# ST-LINK.net
KiCad netlist of a schematic drawn in Altium Designer
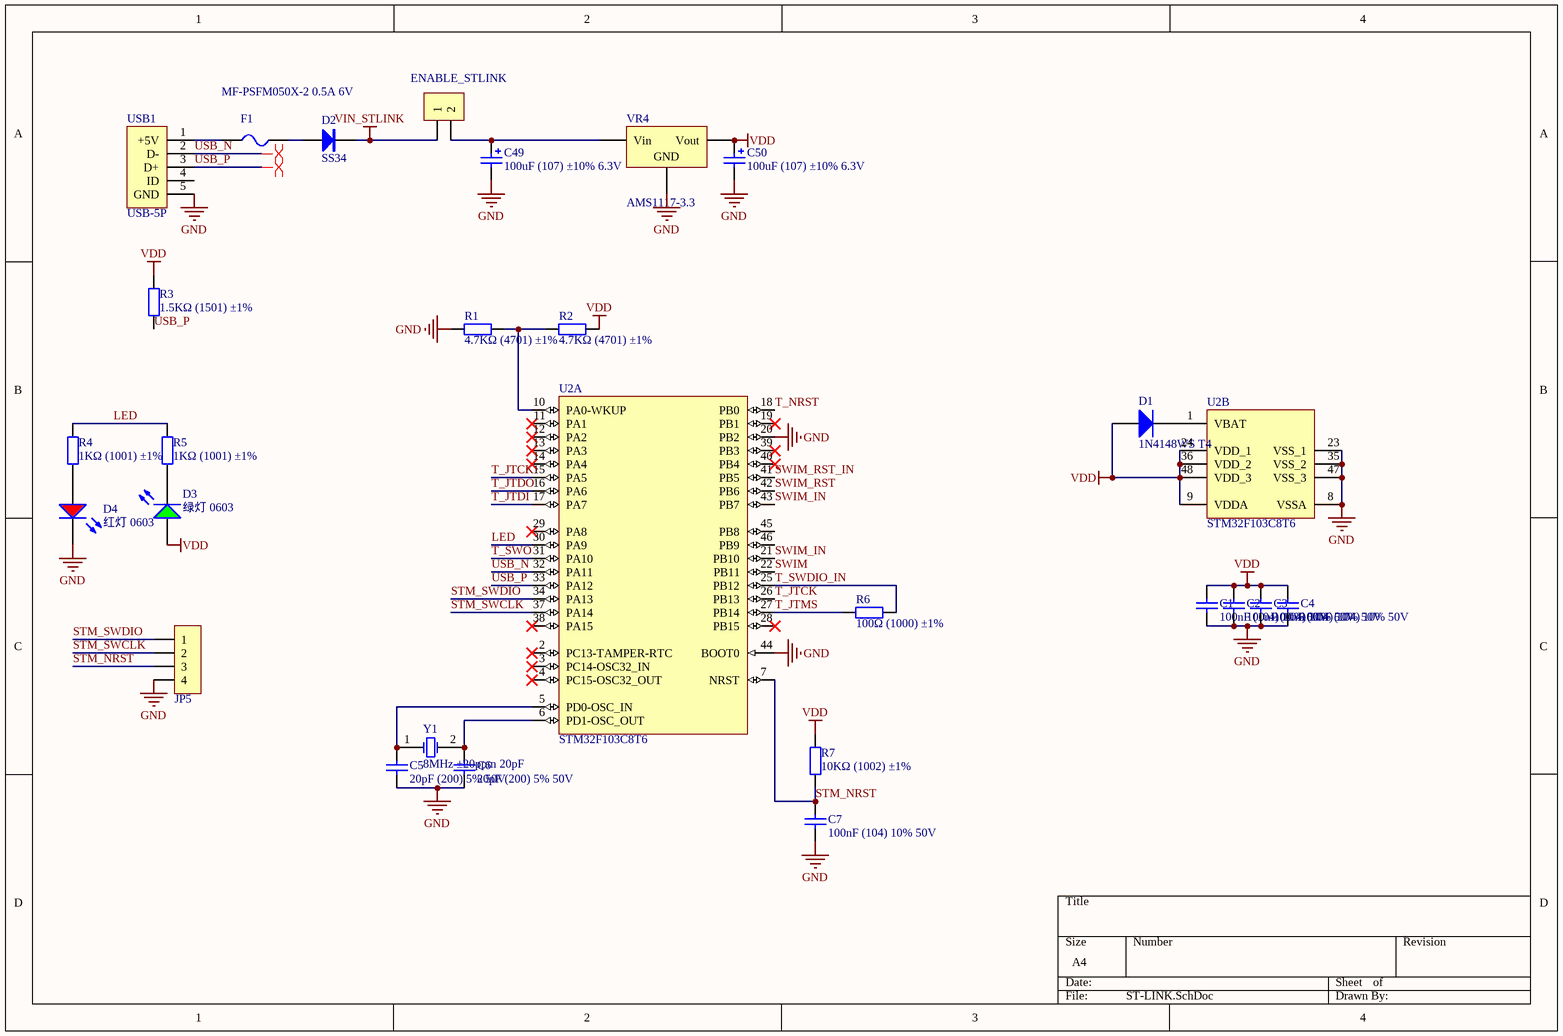
[diagram p0: ST-LINK.SchDoc]

(export (version "E")
  (design (tool "Eeschema 10.0.6"))
  (components
    (comp (ref "C1")
      (value "100nF (104) 10% 50V")
      (footprint "0603_C")
      (description "贴片电容")
      (libsource (lib "Cap") (part "0603 100nF (104) 10% 50V"))
    )
    (comp (ref "C2")
      (value "100nF (104) 10% 50V")
      (footprint "0603_C")
      (description "贴片电容")
      (libsource (lib "Cap") (part "0603 100nF (104) 10% 50V"))
    )
    (comp (ref "C3")
      (value "100nF (104) 10% 50V")
      (footprint "0603_C")
      (description "贴片电容")
      (libsource (lib "Cap") (part "0603 100nF (104) 10% 50V"))
    )
    (comp (ref "C4")
      (value "100nF (104) 10% 50V")
      (footprint "0603_C")
      (description "贴片电容")
      (libsource (lib "Cap") (part "0603 100nF (104) 10% 50V"))
    )
    (comp (ref "C5")
      (value "20pF (200) 5% 50V")
      (footprint "0603_C")
      (description "贴片电容")
      (libsource (lib "Cap") (part "0603 20pF (200) 5% 50V"))
    )
    (comp (ref "C6")
      (value "20pF (200) 5% 50V")
      (footprint "0603_C")
      (description "贴片电容")
      (libsource (lib "Cap") (part "0603 20pF (200) 5% 50V"))
    )
    (comp (ref "C7")
      (value "100nF (104) 10% 50V")
      (footprint "0603_C")
      (description "贴片电容")
      (libsource (lib "Cap") (part "0603 100nF (104) 10% 50V"))
    )
    (comp (ref "C49")
      (value "100uF (107) ±10% 6.3V")
      (footprint "CASE-B_3528")
      (description "钽电容")
      (libsource (lib "Cap") (part "3528 100uF (107) 10% 6.3V"))
    )
    (comp (ref "C50")
      (value "100uF (107) ±10% 6.3V")
      (footprint "CASE-B_3528")
      (description "钽电容")
      (libsource (lib "Cap") (part "3528 100uF (107) 10% 6.3V"))
    )
    (comp (ref "D1")
      (value "1N4148WS T4")
      (footprint "SOD-323")
      (description "二极管")
      (libsource (lib "Diode") (part "SOD-323 1N4148WS T4"))
    )
    (comp (ref "D2")
      (value "SS34")
      (footprint "SMC")
      (description "肖特基二极管")
      (fields (field (name "版权归属") "源创客"))
      (libsource (lib "8.1   - 二极管-整流桥") (part "SS34"))
    )
    (comp (ref "D3")
      (value "绿灯 0603")
      (footprint "0603_LED_S1")
      (description "发光二极管")
      (libsource (lib "LED") (part "0603 绿灯"))
    )
    (comp (ref "D4")
      (value "红灯 0603")
      (footprint "0603_LED_S1")
      (description "发光二极管")
      (libsource (lib "LED") (part "0603 红灯"))
    )
    (comp (ref "ENABLE_STLINK")
      (value "HDR-1X2")
      (footprint "HDR2.54-LI-2P")
      (description "2P接插件")
      (fields (field (name "版权归属") "源创客"))
      (libsource (lib "4.5   - 接插件-脚距2.54") (part "Header 2"))
    )
    (comp (ref "F1")
      (value "MF-PSFM050X-2 0.5A 6V")
      (footprint "FU 0805")
      (description "贴片保险丝")
      (fields (field (name "版权归属") "源创客"))
      (libsource (lib "10.1 - 保险丝-晶振") (part "FU"))
    )
    (comp (ref "JP5")
      (value "HDR-1X4")
      (footprint "HDR2.54-LI-4P")
      (description "4P接插件")
      (fields (field (name "版权归属") "源创客"))
      (libsource (lib "4.5   - 接插件-脚距2.54") (part "Header 4"))
    )
    (comp (ref "R1")
      (value "4.7KΩ (4701) ±1%")
      (footprint "0603_R")
      (description "贴片电阻")
      (libsource (lib "RES") (part "0603 4.7KΩ (4701) 1%"))
    )
    (comp (ref "R2")
      (value "4.7KΩ (4701) ±1%")
      (footprint "0603_R")
      (description "贴片电阻")
      (libsource (lib "RES") (part "0603 4.7KΩ (4701) 1%"))
    )
    (comp (ref "R3")
      (value "1.5KΩ (1501) ±1%")
      (footprint "0603_R")
      (description "贴片电阻")
      (libsource (lib "RES") (part "0603 1.5KΩ (1501) 1%"))
    )
    (comp (ref "R4")
      (value "1KΩ (1001) ±1%")
      (footprint "0603_R")
      (description "贴片电阻")
      (libsource (lib "RES") (part "0603 1KΩ (1001) 1%"))
    )
    (comp (ref "R5")
      (value "1KΩ (1001) ±1%")
      (footprint "0603_R")
      (description "贴片电阻")
      (libsource (lib "RES") (part "0603 1KΩ (1001) 1%"))
    )
    (comp (ref "R6")
      (value "100Ω (1000) ±1%")
      (footprint "0603_R")
      (description "贴片电阻")
      (libsource (lib "RES") (part "0603 100Ω (1000) 1%"))
    )
    (comp (ref "R7")
      (value "10KΩ (1002) ±1%")
      (footprint "0603_R")
      (description "贴片电阻")
      (libsource (lib "RES") (part "0603 10KΩ (1002) 1%"))
    )
    (comp (ref "U2")
      (value "STM32F103C8T6")
      (footprint "STM-LQFP48_L")
      (libsource (lib "Altium Content Vault") (part "MC-ARM-STM32F103X8_B-SQ48"))
    )
    (comp (ref "USB1")
      (value "USB-5P")
      (footprint "USB-MICRO_D")
      (description "微型USB母座")
      (fields (field (name "版权归属") "源创客"))
      (libsource (lib "4.1   - 接口类") (part "USB-5P"))
    )
    (comp (ref "VR4")
      (value "AMS1117-3.3")
      (footprint "SOT-223")
      (description "低压差线性稳压(LDO)")
      (libsource (lib "LDO") (part "SOT-223 AMS1117-3.3"))
    )
    (comp (ref "Y1")
      (value "8MHz ±20ppm 20pF")
      (footprint "SMD-5032_2P")
      (description "贴片晶振")
      (libsource (lib "CrystalOscillator") (part "SMD-5032_2P 8MHz 20ppm 20pF"))
    )
  )
  (nets
    (net (code "1") (name "/LED") (class "Default")
      (node (ref "R4") (pin "2") (pinfunction "2_2") (pintype "passive"))
      (node (ref "R5") (pin "2") (pinfunction "2_2") (pintype "passive"))
      (node (ref "U2") (pin "30") (pinfunction "PA9_30") (pintype "bidirectional"))
    )
    (net (code "2") (name "/STM_NRST") (class "Default")
      (node (ref "C7") (pin "2") (pinfunction "2_2") (pintype "passive"))
      (node (ref "JP5") (pin "3") (pinfunction "3_3") (pintype "passive"))
      (node (ref "R7") (pin "1") (pinfunction "1_1") (pintype "passive"))
      (node (ref "U2") (pin "7") (pinfunction "NRST_7") (pintype "bidirectional"))
    )
    (net (code "3") (name "/STM_SWCLK") (class "Default")
      (node (ref "JP5") (pin "2") (pinfunction "2_2") (pintype "passive"))
      (node (ref "U2") (pin "37") (pinfunction "PA14_37") (pintype "bidirectional"))
    )
    (net (code "4") (name "/STM_SWDIO") (class "Default")
      (node (ref "JP5") (pin "1") (pinfunction "1_1") (pintype "passive"))
      (node (ref "U2") (pin "34") (pinfunction "PA13_34") (pintype "bidirectional"))
    )
    (net (code "5") (name "/SWIM") (class "Default")
      (node (ref "U2") (pin "22") (pinfunction "PB11_22") (pintype "bidirectional"))
    )
    (net (code "6") (name "/SWIM_IN") (class "Default")
      (node (ref "U2") (pin "21") (pinfunction "PB10_21") (pintype "bidirectional"))
      (node (ref "U2") (pin "43") (pinfunction "PB7_43") (pintype "bidirectional"))
    )
    (net (code "7") (name "/SWIM_RST") (class "Default")
      (node (ref "U2") (pin "42") (pinfunction "PB6_42") (pintype "bidirectional"))
    )
    (net (code "8") (name "/SWIM_RST_IN") (class "Default")
      (node (ref "U2") (pin "41") (pinfunction "PB5_41") (pintype "bidirectional"))
    )
    (net (code "9") (name "/T_JTCK") (class "Default")
      (node (ref "U2") (pin "15") (pinfunction "PA5_15") (pintype "bidirectional"))
      (node (ref "U2") (pin "26") (pinfunction "PB13_26") (pintype "bidirectional"))
    )
    (net (code "10") (name "/T_JTDI") (class "Default")
      (node (ref "U2") (pin "17") (pinfunction "PA7_17") (pintype "bidirectional"))
    )
    (net (code "11") (name "/T_JTDO") (class "Default")
      (node (ref "U2") (pin "16") (pinfunction "PA6_16") (pintype "bidirectional"))
    )
    (net (code "12") (name "/T_JTMS") (class "Default")
      (node (ref "R6") (pin "1") (pinfunction "1_1") (pintype "passive"))
      (node (ref "U2") (pin "27") (pinfunction "PB14_27") (pintype "bidirectional"))
    )
    (net (code "13") (name "/T_NRST") (class "Default")
      (node (ref "U2") (pin "18") (pinfunction "PB0_18") (pintype "bidirectional"))
    )
    (net (code "14") (name "/T_SWDIO_IN") (class "Default")
      (node (ref "R6") (pin "2") (pinfunction "2_2") (pintype "passive"))
      (node (ref "U2") (pin "25") (pinfunction "PB12_25") (pintype "bidirectional"))
    )
    (net (code "15") (name "/T_SWO") (class "Default")
      (node (ref "U2") (pin "31") (pinfunction "PA10_31") (pintype "bidirectional"))
    )
    (net (code "16") (name "/USB_N") (class "Default")
      (node (ref "U2") (pin "32") (pinfunction "PA11_32") (pintype "bidirectional"))
      (node (ref "USB1") (pin "2") (pinfunction "D-_2") (pintype "passive"))
    )
    (net (code "17") (name "/USB_P") (class "Default")
      (node (ref "R3") (pin "1") (pinfunction "1_1") (pintype "passive"))
      (node (ref "U2") (pin "33") (pinfunction "PA12_33") (pintype "bidirectional"))
      (node (ref "USB1") (pin "3") (pinfunction "D+_3") (pintype "passive"))
    )
    (net (code "18") (name "GND") (class "Default")
      (node (ref "C1") (pin "1") (pinfunction "1_1") (pintype "passive"))
      (node (ref "C2") (pin "1") (pinfunction "1_1") (pintype "passive"))
      (node (ref "C3") (pin "1") (pinfunction "1_1") (pintype "passive"))
      (node (ref "C4") (pin "1") (pinfunction "1_1") (pintype "passive"))
      (node (ref "C49") (pin "2") (pinfunction "2_2") (pintype "passive"))
      (node (ref "C5") (pin "1") (pinfunction "1_1") (pintype "passive"))
      (node (ref "C50") (pin "2") (pinfunction "2_2") (pintype "passive"))
      (node (ref "C6") (pin "1") (pinfunction "1_1") (pintype "passive"))
      (node (ref "C7") (pin "1") (pinfunction "1_1") (pintype "passive"))
      (node (ref "D4") (pin "K") (pinfunction "K_K") (pintype "passive"))
      (node (ref "JP5") (pin "4") (pinfunction "4_4") (pintype "passive"))
      (node (ref "R1") (pin "1") (pinfunction "1_1") (pintype "passive"))
      (node (ref "U2") (pin "20") (pinfunction "PB2_20") (pintype "bidirectional"))
      (node (ref "U2") (pin "23") (pinfunction "VSS_1_23") (pintype "power_in"))
      (node (ref "U2") (pin "35") (pinfunction "VSS_2_35") (pintype "power_in"))
      (node (ref "U2") (pin "44") (pinfunction "BOOT0_44") (pintype "input"))
      (node (ref "U2") (pin "47") (pinfunction "VSS_3_47") (pintype "power_in"))
      (node (ref "U2") (pin "8") (pinfunction "VSSA_8") (pintype "power_in"))
      (node (ref "USB1") (pin "5") (pinfunction "GND_5") (pintype "passive"))
      (node (ref "VR4") (pin "1") (pinfunction "GND_1") (pintype "passive"))
    )
    (net (code "19") (name "Net-(D1-K)") (class "Default")
      (node (ref "D1") (pin "2") (pinfunction "K_2") (pintype "passive"))
      (node (ref "U2") (pin "1") (pinfunction "VBAT_1") (pintype "power_in"))
    )
    (net (code "20") (name "Net-(D2-A)") (class "Default")
      (node (ref "D2") (pin "1") (pinfunction "A_1") (pintype "passive"))
      (node (ref "F1") (pin "2") (pinfunction "2_2") (pintype "passive"))
    )
    (net (code "21") (name "Net-(D3-PadK)") (class "Default")
      (node (ref "D3") (pin "K") (pinfunction "K_K") (pintype "passive"))
      (node (ref "R5") (pin "1") (pinfunction "1_1") (pintype "passive"))
    )
    (net (code "22") (name "Net-(D4-PadA)") (class "Default")
      (node (ref "D4") (pin "A") (pinfunction "A_A") (pintype "passive"))
      (node (ref "R4") (pin "1") (pinfunction "1_1") (pintype "passive"))
    )
    (net (code "23") (name "Net-(U2A-PA0-WKUP)") (class "Default")
      (node (ref "R1") (pin "2") (pinfunction "2_2") (pintype "passive"))
      (node (ref "R2") (pin "1") (pinfunction "1_1") (pintype "passive"))
      (node (ref "U2") (pin "10") (pinfunction "PA0-WKUP_10") (pintype "bidirectional"))
    )
    (net (code "24") (name "Net-(U2A-PD0-OSC_IN)") (class "Default")
      (node (ref "C5") (pin "2") (pinfunction "2_2") (pintype "passive"))
      (node (ref "U2") (pin "5") (pinfunction "PD0-OSC_IN_5") (pintype "bidirectional"))
      (node (ref "Y1") (pin "1") (pinfunction "OSC1_1") (pintype "passive"))
    )
    (net (code "25") (name "Net-(U2A-PD1-OSC_OUT)") (class "Default")
      (node (ref "C6") (pin "2") (pinfunction "2_2") (pintype "passive"))
      (node (ref "U2") (pin "6") (pinfunction "PD1-OSC_OUT_6") (pintype "bidirectional"))
      (node (ref "Y1") (pin "2") (pinfunction "OSC2_2") (pintype "passive"))
    )
    (net (code "26") (name "Net-(USB1-+5V)") (class "Default")
      (node (ref "F1") (pin "1") (pinfunction "1_1") (pintype "passive"))
      (node (ref "USB1") (pin "1") (pinfunction "+5V_1") (pintype "passive"))
    )
    (net (code "27") (name "Net-(VR4-Vin)") (class "Default")
      (node (ref "C49") (pin "1") (pinfunction "1_1") (pintype "passive"))
      (node (ref "ENABLE_STLINK") (pin "2") (pinfunction "2_2") (pintype "passive"))
      (node (ref "VR4") (pin "3") (pinfunction "Vin_3") (pintype "passive"))
    )
    (net (code "28") (name "VDD") (class "Default")
      (node (ref "C1") (pin "2") (pinfunction "2_2") (pintype "passive"))
      (node (ref "C2") (pin "2") (pinfunction "2_2") (pintype "passive"))
      (node (ref "C3") (pin "2") (pinfunction "2_2") (pintype "passive"))
      (node (ref "C4") (pin "2") (pinfunction "2_2") (pintype "passive"))
      (node (ref "C50") (pin "1") (pinfunction "1_1") (pintype "passive"))
      (node (ref "D1") (pin "1") (pinfunction "A_1") (pintype "passive"))
      (node (ref "D3") (pin "A") (pinfunction "A_A") (pintype "passive"))
      (node (ref "R2") (pin "2") (pinfunction "2_2") (pintype "passive"))
      (node (ref "R3") (pin "2") (pinfunction "2_2") (pintype "passive"))
      (node (ref "R7") (pin "2") (pinfunction "2_2") (pintype "passive"))
      (node (ref "U2") (pin "24") (pinfunction "VDD_1_24") (pintype "power_in"))
      (node (ref "U2") (pin "36") (pinfunction "VDD_2_36") (pintype "power_in"))
      (node (ref "U2") (pin "48") (pinfunction "VDD_3_48") (pintype "power_in"))
      (node (ref "U2") (pin "9") (pinfunction "VDDA_9") (pintype "power_in"))
      (node (ref "VR4") (pin "2") (pinfunction "Vout_2") (pintype "passive"))
    )
    (net (code "29") (name "VIN_STLINK") (class "Default")
      (node (ref "D2") (pin "2") (pinfunction "K_2") (pintype "passive"))
      (node (ref "ENABLE_STLINK") (pin "1") (pinfunction "1_1") (pintype "passive"))
    )
    (net (code "30") (name "unconnected-(U2A-PA1-Pad11)") (class "Default")
      (node (ref "U2") (pin "11") (pinfunction "PA1_11") (pintype "bidirectional+no_connect"))
    )
    (net (code "31") (name "unconnected-(U2A-PA2-Pad12)") (class "Default")
      (node (ref "U2") (pin "12") (pinfunction "PA2_12") (pintype "bidirectional+no_connect"))
    )
    (net (code "32") (name "unconnected-(U2A-PA3-Pad13)") (class "Default")
      (node (ref "U2") (pin "13") (pinfunction "PA3_13") (pintype "bidirectional+no_connect"))
    )
    (net (code "33") (name "unconnected-(U2A-PA4-Pad14)") (class "Default")
      (node (ref "U2") (pin "14") (pinfunction "PA4_14") (pintype "bidirectional+no_connect"))
    )
    (net (code "34") (name "unconnected-(U2A-PA8-Pad29)") (class "Default")
      (node (ref "U2") (pin "29") (pinfunction "PA8_29") (pintype "bidirectional+no_connect"))
    )
    (net (code "35") (name "unconnected-(U2A-PA15-Pad38)") (class "Default")
      (node (ref "U2") (pin "38") (pinfunction "PA15_38") (pintype "bidirectional+no_connect"))
    )
    (net (code "36") (name "unconnected-(U2A-PB1-Pad19)") (class "Default")
      (node (ref "U2") (pin "19") (pinfunction "PB1_19") (pintype "bidirectional+no_connect"))
    )
    (net (code "37") (name "unconnected-(U2A-PB3-Pad39)") (class "Default")
      (node (ref "U2") (pin "39") (pinfunction "PB3_39") (pintype "bidirectional+no_connect"))
    )
    (net (code "38") (name "unconnected-(U2A-PB4-Pad40)") (class "Default")
      (node (ref "U2") (pin "40") (pinfunction "PB4_40") (pintype "bidirectional+no_connect"))
    )
    (net (code "39") (name "unconnected-(U2A-PB8-Pad45)") (class "Default")
      (node (ref "U2") (pin "45") (pinfunction "PB8_45") (pintype "bidirectional"))
    )
    (net (code "40") (name "unconnected-(U2A-PB9-Pad46)") (class "Default")
      (node (ref "U2") (pin "46") (pinfunction "PB9_46") (pintype "bidirectional"))
    )
    (net (code "41") (name "unconnected-(U2A-PB15-Pad28)") (class "Default")
      (node (ref "U2") (pin "28") (pinfunction "PB15_28") (pintype "bidirectional+no_connect"))
    )
    (net (code "42") (name "unconnected-(U2A-PC13-TAMPER-RTC-Pad2)") (class "Default")
      (node (ref "U2") (pin "2") (pinfunction "PC13-TAMPER-RTC_2") (pintype "bidirectional+no_connect"))
    )
    (net (code "43") (name "unconnected-(U2A-PC14-OSC32_IN-Pad3)") (class "Default")
      (node (ref "U2") (pin "3") (pinfunction "PC14-OSC32_IN_3") (pintype "bidirectional+no_connect"))
    )
    (net (code "44") (name "unconnected-(U2A-PC15-OSC32_OUT-Pad4)") (class "Default")
      (node (ref "U2") (pin "4") (pinfunction "PC15-OSC32_OUT_4") (pintype "bidirectional+no_connect"))
    )
    (net (code "45") (name "unconnected-(USB1-ID-Pad4)") (class "Default")
      (node (ref "USB1") (pin "4") (pinfunction "ID_4") (pintype "passive"))
    )
  )
)
